# IMx6Q_EX.net
KiCad netlist of a schematic drawn in Altium Designer
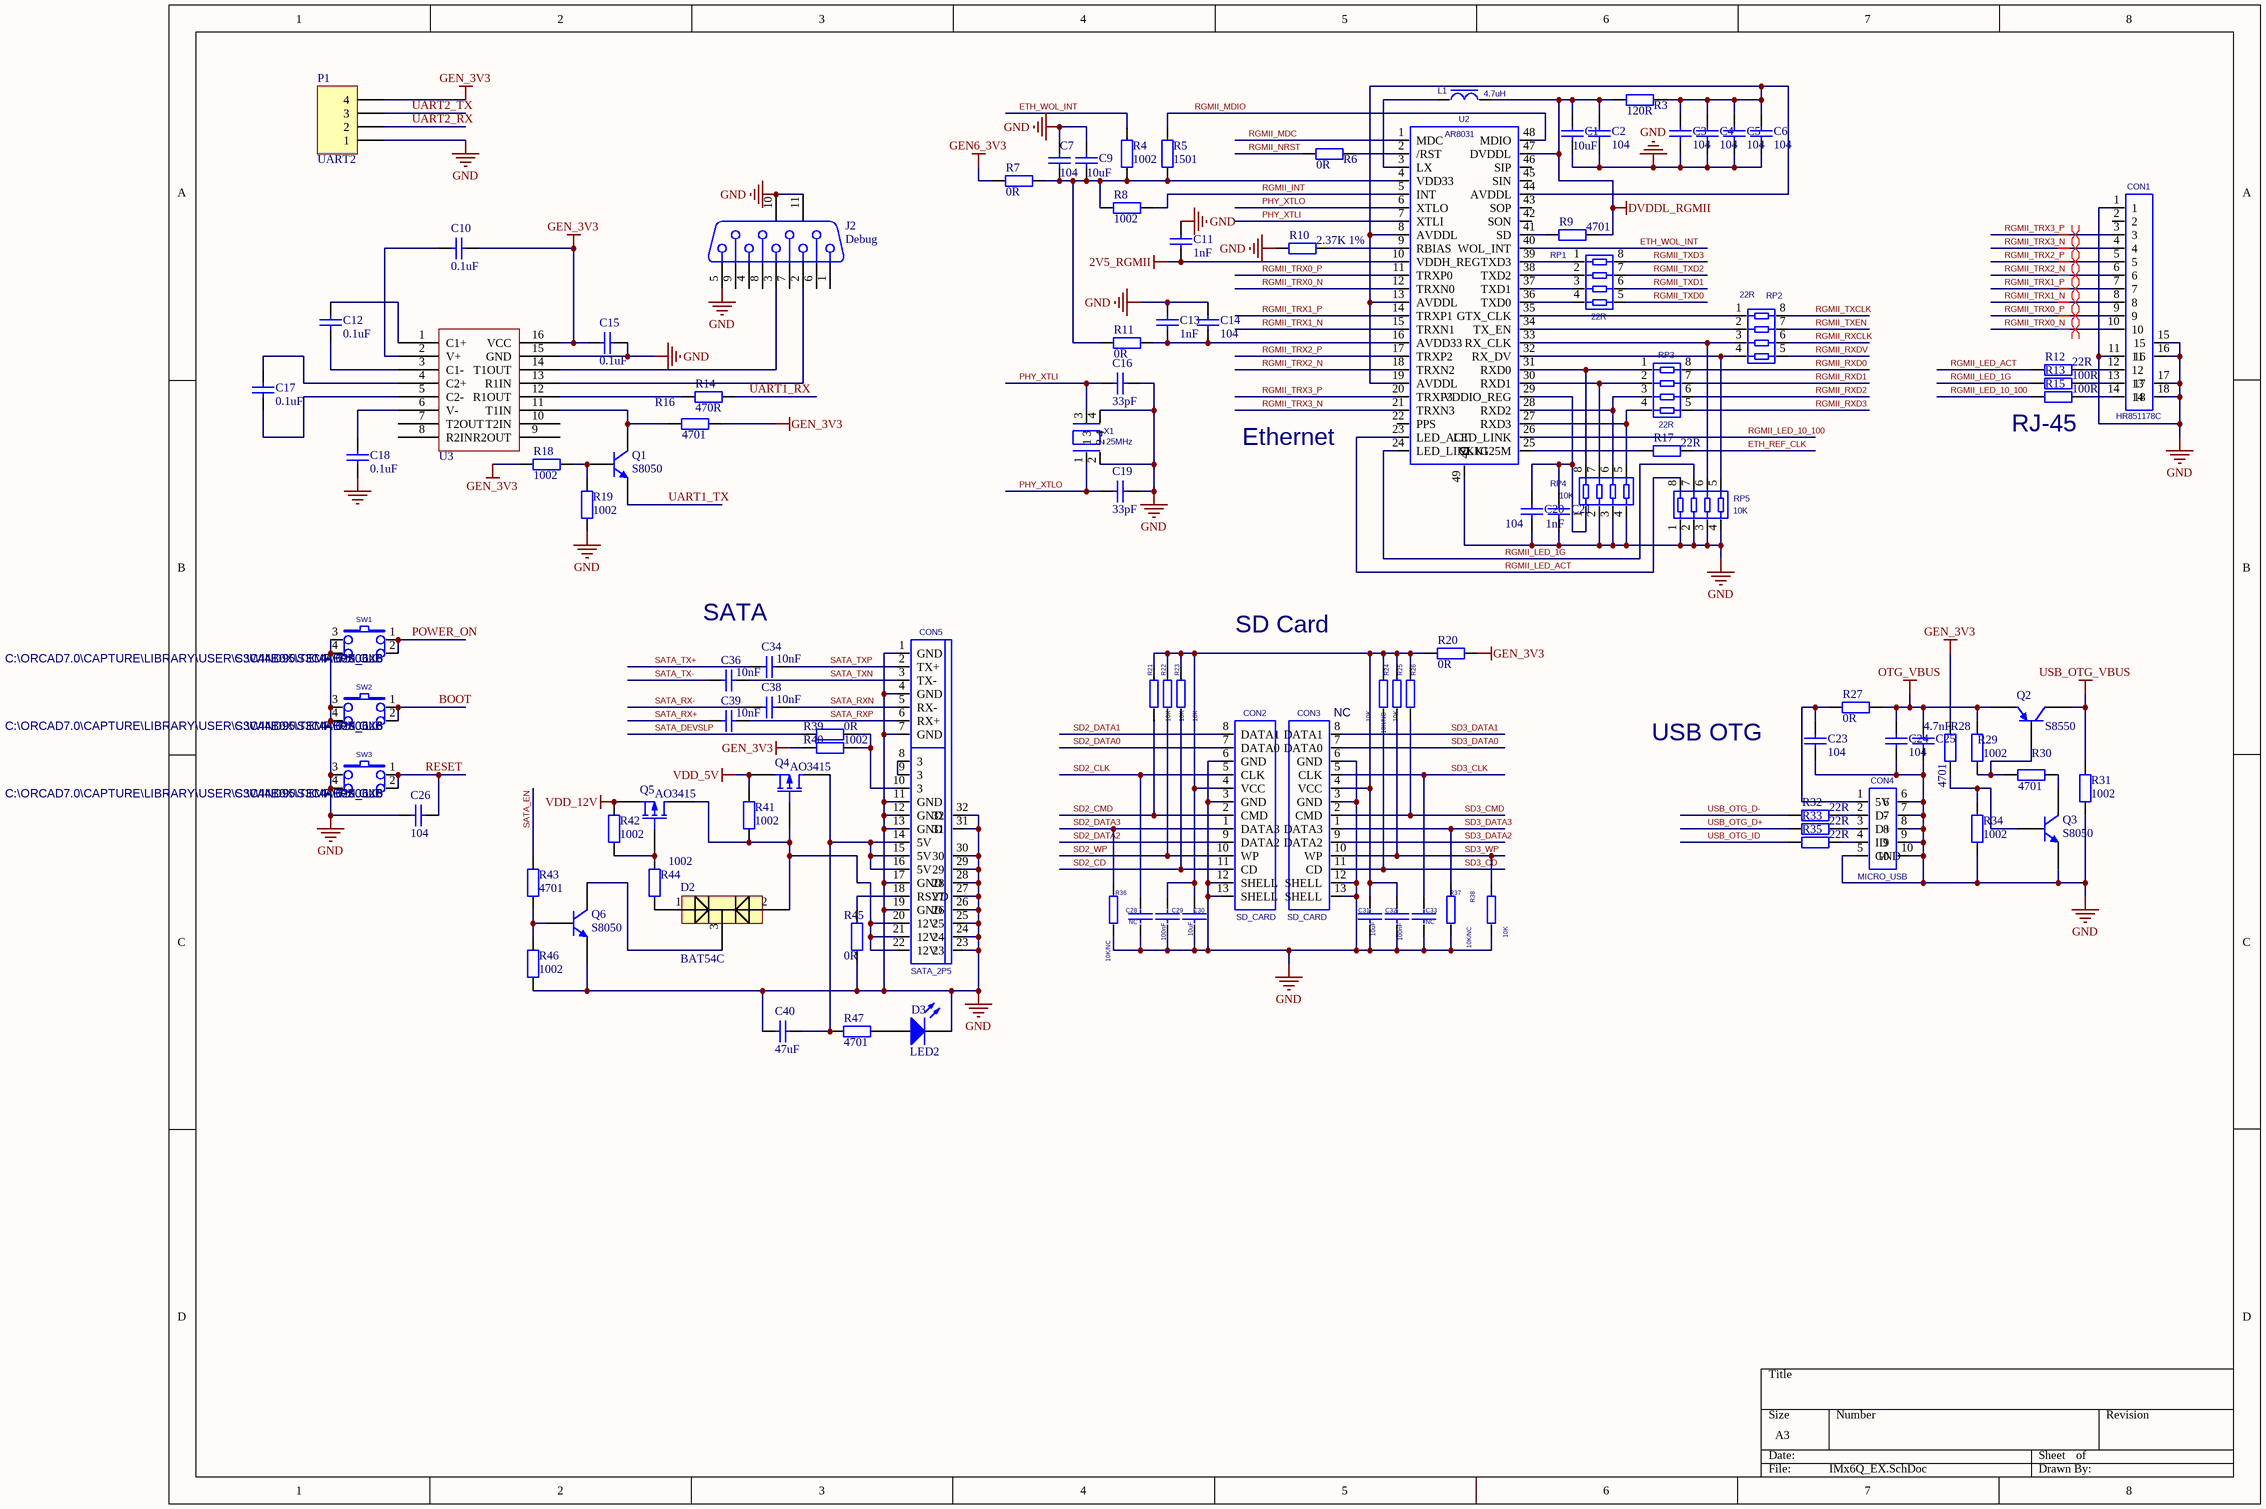
[diagram p0: IMx6Q_EX.SchDoc]

(export (version "E")
  (design (tool "Eeschema 10.0.6"))
  (components
    (comp (ref "C1")
      (value "10uF")
      (footprint "0805C")
      (description "Capacitor")
      (libsource (lib "Miscellaneous Devices") (part "Cap"))
    )
    (comp (ref "C2")
      (value "104")
      (footprint "0805C")
      (description "Capacitor")
      (libsource (lib "Miscellaneous Devices") (part "Cap"))
    )
    (comp (ref "C3")
      (value "104")
      (footprint "0805C")
      (description "Capacitor")
      (libsource (lib "Miscellaneous Devices") (part "Cap"))
    )
    (comp (ref "C4")
      (value "104")
      (footprint "0805C")
      (description "Capacitor")
      (libsource (lib "Miscellaneous Devices") (part "Cap"))
    )
    (comp (ref "C5")
      (value "104")
      (footprint "0805C")
      (description "Capacitor")
      (libsource (lib "Miscellaneous Devices") (part "Cap"))
    )
    (comp (ref "C6")
      (value "104")
      (footprint "0805C")
      (description "Capacitor")
      (libsource (lib "Miscellaneous Devices") (part "Cap"))
    )
    (comp (ref "C7")
      (value "104")
      (footprint "0805C")
      (description "Capacitor")
      (libsource (lib "Miscellaneous Devices") (part "Cap"))
    )
    (comp (ref "C9")
      (value "10uF")
      (footprint "0805C")
      (description "Capacitor")
      (libsource (lib "Miscellaneous Devices") (part "Cap"))
    )
    (comp (ref "C10") (value "0.1uF") (footprint "0805C") (libsource (lib "贴片电容电阻等") (part "电容")))
    (comp (ref "C11")
      (value "1nF")
      (footprint "0805C")
      (description "Capacitor")
      (libsource (lib "Miscellaneous Devices") (part "Cap"))
    )
    (comp (ref "C12") (value "0.1uF") (footprint "0805C") (libsource (lib "贴片电容电阻等") (part "电容")))
    (comp (ref "C13")
      (value "1nF")
      (footprint "0805C")
      (description "Capacitor")
      (libsource (lib "Miscellaneous Devices") (part "Cap"))
    )
    (comp (ref "C14")
      (value "104")
      (footprint "0805C")
      (description "Capacitor")
      (libsource (lib "Miscellaneous Devices") (part "Cap"))
    )
    (comp (ref "C15") (value "0.1uF") (footprint "0805C") (libsource (lib "贴片电容电阻等") (part "电容")))
    (comp (ref "C16")
      (value "33pF")
      (footprint "0805C")
      (description "Capacitor")
      (libsource (lib "Miscellaneous Devices") (part "Cap"))
    )
    (comp (ref "C17") (value "0.1uF") (footprint "0805C") (libsource (lib "贴片电容电阻等") (part "电容")))
    (comp (ref "C18") (value "0.1uF") (footprint "0805C") (libsource (lib "贴片电容电阻等") (part "电容")))
    (comp (ref "C19")
      (value "33pF")
      (footprint "0805C")
      (description "Capacitor")
      (libsource (lib "Miscellaneous Devices") (part "Cap"))
    )
    (comp (ref "C20")
      (value "104")
      (footprint "0805C")
      (description "Capacitor")
      (libsource (lib "Miscellaneous Devices") (part "Cap"))
    )
    (comp (ref "C21")
      (value "1nF")
      (footprint "0805C")
      (description "Capacitor")
      (libsource (lib "Miscellaneous Devices") (part "Cap"))
    )
    (comp (ref "C23")
      (value "104")
      (footprint "0805C")
      (description "Capacitor")
      (libsource (lib "Miscellaneous Devices") (part "Cap"))
    )
    (comp (ref "C24")
      (value "104")
      (footprint "0805C")
      (description "Capacitor")
      (libsource (lib "Miscellaneous Devices") (part "Cap"))
    )
    (comp (ref "C25")
      (value "4.7nF")
      (footprint "0805C")
      (description "Capacitor")
      (libsource (lib "Miscellaneous Devices") (part "Cap"))
    )
    (comp (ref "C26")
      (value "104")
      (footprint "0805C")
      (description "Capacitor")
      (libsource (lib "Miscellaneous Devices") (part "Cap"))
    )
    (comp (ref "C28")
      (value "NC")
      (footprint "0805C")
      (fields (field (name "Comment") "C_0603"))
      (libsource (lib "*") (part "C_0603"))
    )
    (comp (ref "C29")
      (value "100nF")
      (footprint "0805C")
      (fields (field (name "Comment") "C_0603"))
      (libsource (lib "*") (part "C_0603"))
    )
    (comp (ref "C30")
      (value "10uF")
      (footprint "0805C")
      (fields (field (name "Comment") "C_0603"))
      (libsource (lib "*") (part "C_0603"))
    )
    (comp (ref "C31")
      (value "10uF")
      (footprint "0805C")
      (fields (field (name "Comment") "C_0603"))
      (libsource (lib "*") (part "C_0603"))
    )
    (comp (ref "C32")
      (value "100nF")
      (footprint "0805C")
      (fields (field (name "Comment") "C_0603"))
      (libsource (lib "*") (part "C_0603"))
    )
    (comp (ref "C33")
      (value "NC")
      (footprint "0805C")
      (fields (field (name "Comment") "C_0603"))
      (libsource (lib "*") (part "C_0603"))
    )
    (comp (ref "C34")
      (value "10nF")
      (footprint "0805C")
      (description "Capacitor")
      (libsource (lib "Miscellaneous Devices") (part "Cap"))
    )
    (comp (ref "C36")
      (value "10nF")
      (footprint "0805C")
      (description "Capacitor")
      (libsource (lib "Miscellaneous Devices") (part "Cap"))
    )
    (comp (ref "C38")
      (value "10nF")
      (footprint "0805C")
      (description "Capacitor")
      (libsource (lib "Miscellaneous Devices") (part "Cap"))
    )
    (comp (ref "C39")
      (value "10nF")
      (footprint "0805C")
      (description "Capacitor")
      (libsource (lib "Miscellaneous Devices") (part "Cap"))
    )
    (comp (ref "C40")
      (value "47uF")
      (footprint "0805C")
      (description "Capacitor")
      (libsource (lib "Miscellaneous Devices") (part "Cap"))
    )
    (comp (ref "CON1") (value "HR851178C") (footprint "HR851178C") (libsource (lib "*") (part "HR851178C")))
    (comp (ref "CON2") (value "SD_CARD") (footprint "SD_CARD") (libsource (lib "*") (part "SD_CARD")))
    (comp (ref "CON3") (value "SD_CARD") (footprint "SD_CARD") (libsource (lib "*") (part "SD_CARD")))
    (comp (ref "CON4") (value "MICRO_USB") (footprint "MICRO_USB") (libsource (lib "*") (part "MICRO_USB")))
    (comp (ref "CON5")
      (value "SATA_2P5")
      (footprint "SATA_MICRO_2P5")
      (libsource (lib "*") (part "SATA_2P5"))
    )
    (comp (ref "D2") (value "BAT54C") (footprint "SOT-23-3") (libsource (lib "Schlib1") (part "BAT54C")))
    (comp (ref "D3")
      (value "LED2")
      (footprint "0805_LED")
      (description "Typical RED, GREEN, YELLOW, AMBER GaAs LED")
      (libsource (lib "Miscellaneous Devices") (part "LED2"))
    )
    (comp (ref "J2")
      (value "Debug")
      (footprint "DSUB1.385-2H9")
      (description "Receptacle Assembly, 9 Position, Right Angle")
      (libsource (lib "Miscellaneous Connectors") (part "D Connector 9"))
    )
    (comp (ref "L1")
      (value "4.7uH")
      (footprint "L_3-3")
      (fields (field (name "Comment") "L_3-3"))
      (libsource (lib "*") (part "L_3-3"))
    )
    (comp (ref "P1")
      (value "UART2")
      (footprint "HDR1X4")
      (description "Header, 4-Pin")
      (libsource (lib "Miscellaneous Connectors") (part "Header 4"))
    )
    (comp (ref "Q1")
      (value "S8050")
      (footprint "SOT23")
      (description "NPN General Purpose Amplifier")
      (libsource (lib "Miscellaneous Devices") (part "2N3904"))
    )
    (comp (ref "Q2")
      (value "S8550")
      (footprint "SOT23-S8550")
      (description "PNP Bipolar Transistor")
      (libsource (lib "Miscellaneous Devices") (part "PNP"))
    )
    (comp (ref "Q3")
      (value "S8050")
      (footprint "SOT23")
      (description "NPN General Purpose Amplifier")
      (libsource (lib "Miscellaneous Devices") (part "2N3904"))
    )
    (comp (ref "Q4")
      (value "AO3415")
      (footprint "SOT23-AO3415")
      (description "P-Channel MOSFET")
      (libsource (lib "Miscellaneous Devices") (part "MOSFET-P"))
    )
    (comp (ref "Q5")
      (value "AO3415")
      (footprint "SOT23-AO3415")
      (description "P-Channel MOSFET")
      (libsource (lib "Miscellaneous Devices") (part "MOSFET-P"))
    )
    (comp (ref "Q6")
      (value "S8050")
      (footprint "SOT23-AO3415")
      (description "NPN Bipolar Transistor")
      (libsource (lib "Miscellaneous Devices") (part "NPN"))
    )
    (comp (ref "R3") (value "120R") (footprint "0805R") (libsource (lib "") (part "电阻_1")))
    (comp (ref "R4") (value "1002") (footprint "0805R") (libsource (lib "贴片电容电阻等") (part "电阻")))
    (comp (ref "R5") (value "1501") (footprint "0805R") (libsource (lib "贴片电容电阻等") (part "电阻")))
    (comp (ref "R6") (value "0R") (footprint "0805R") (libsource (lib "") (part "电阻_1")))
    (comp (ref "R7") (value "0R") (footprint "0805R") (libsource (lib "") (part "电阻_1")))
    (comp (ref "R8") (value "1002") (footprint "0805R") (libsource (lib "") (part "电阻_2")))
    (comp (ref "R9")
      (value "4701")
      (footprint "0805R")
      (description "Resistor")
      (libsource (lib "Miscellaneous Devices") (part "Res2"))
    )
    (comp (ref "R10") (value "2.37K 1%") (footprint "0805R") (libsource (lib "") (part "电阻_1")))
    (comp (ref "R11") (value "0R") (footprint "0805R") (libsource (lib "") (part "电阻_1")))
    (comp (ref "R12")
      (value "22R")
      (footprint "0805R")
      (description "Resistor")
      (libsource (lib "Miscellaneous Devices") (part "Res2"))
    )
    (comp (ref "R13")
      (value "100R")
      (footprint "0805R")
      (description "Resistor")
      (libsource (lib "Miscellaneous Devices") (part "Res2"))
    )
    (comp (ref "R14") (value "470R") (footprint "0805R") (libsource (lib "") (part "电阻_1")))
    (comp (ref "R15")
      (value "100R")
      (footprint "0805R")
      (description "Resistor")
      (libsource (lib "Miscellaneous Devices") (part "Res2"))
    )
    (comp (ref "R16")
      (value "4701")
      (footprint "0805R")
      (description "Resistor")
      (libsource (lib "Miscellaneous Devices") (part "Res2"))
    )
    (comp (ref "R17")
      (value "22R")
      (footprint "0805R")
      (description "Resistor")
      (libsource (lib "Miscellaneous Devices") (part "Res2"))
    )
    (comp (ref "R18")
      (value "1002")
      (footprint "0805R")
      (description "Resistor")
      (libsource (lib "Miscellaneous Devices") (part "Res2"))
    )
    (comp (ref "R19")
      (value "1002")
      (footprint "0805R")
      (description "Resistor")
      (libsource (lib "") (part "Res2_2"))
    )
    (comp (ref "R20") (value "0R") (footprint "0805R") (libsource (lib "") (part "电阻_1")))
    (comp (ref "R21")
      (value "10K")
      (footprint "0805R")
      (fields (field (name "Comment") "R_0603"))
      (libsource (lib "*") (part "R_0603"))
    )
    (comp (ref "R22")
      (value "10K")
      (footprint "0805R")
      (fields (field (name "Comment") "R_0603"))
      (libsource (lib "*") (part "R_0603"))
    )
    (comp (ref "R23")
      (value "10K")
      (footprint "0805R")
      (fields (field (name "Comment") "R_0603"))
      (libsource (lib "*") (part "R_0603"))
    )
    (comp (ref "R24")
      (value "10K")
      (footprint "0805R")
      (fields (field (name "Comment") "R_0603"))
      (libsource (lib "*") (part "R_0603"))
    )
    (comp (ref "R25")
      (value "10K/NC")
      (footprint "0805R")
      (fields (field (name "Comment") "R_0603"))
      (libsource (lib "*") (part "R_0603"))
    )
    (comp (ref "R26")
      (value "10K")
      (footprint "0805R")
      (fields (field (name "Comment") "R_0603"))
      (libsource (lib "*") (part "R_0603"))
    )
    (comp (ref "R27") (value "0R") (footprint "0805R") (libsource (lib "") (part "电阻_1")))
    (comp (ref "R28") (value "4701") (footprint "0805R") (libsource (lib "贴片电容电阻等") (part "电阻")))
    (comp (ref "R29") (value "1002") (footprint "0805R") (libsource (lib "贴片电容电阻等") (part "电阻")))
    (comp (ref "R30") (value "4701") (footprint "0805R") (libsource (lib "") (part "电阻_2")))
    (comp (ref "R31") (value "1002") (footprint "0805R") (libsource (lib "贴片电容电阻等") (part "电阻")))
    (comp (ref "R32")
      (value "22R")
      (footprint "0805R")
      (description "Resistor")
      (libsource (lib "Miscellaneous Devices") (part "Res2"))
    )
    (comp (ref "R33")
      (value "22R")
      (footprint "0805R")
      (description "Resistor")
      (libsource (lib "Miscellaneous Devices") (part "Res2"))
    )
    (comp (ref "R34") (value "1002") (footprint "0805R") (libsource (lib "贴片电容电阻等") (part "电阻")))
    (comp (ref "R35")
      (value "22R")
      (footprint "0805R")
      (description "Resistor")
      (libsource (lib "Miscellaneous Devices") (part "Res2"))
    )
    (comp (ref "R36")
      (value "10K/NC")
      (footprint "0805R")
      (fields (field (name "Comment") "R_0603"))
      (libsource (lib "*") (part "R_0603"))
    )
    (comp (ref "R37")
      (value "10K/NC")
      (footprint "0805R")
      (fields (field (name "Comment") "R_0603"))
      (libsource (lib "*") (part "R_0603"))
    )
    (comp (ref "R38")
      (value "10K")
      (footprint "0805R")
      (fields (field (name "Comment") "R_0603"))
      (libsource (lib "*") (part "R_0603"))
    )
    (comp (ref "R39")
      (value "0R")
      (footprint "0805R")
      (description "Resistor")
      (libsource (lib "Miscellaneous Devices") (part "Res2"))
    )
    (comp (ref "R40")
      (value "1002")
      (footprint "0805R")
      (description "Resistor")
      (libsource (lib "Miscellaneous Devices") (part "Res2"))
    )
    (comp (ref "R41")
      (value "1002")
      (footprint "0805R")
      (description "Resistor")
      (libsource (lib "") (part "Res2_2"))
    )
    (comp (ref "R42")
      (value "1002")
      (footprint "0805R")
      (description "Resistor")
      (libsource (lib "") (part "Res2_2"))
    )
    (comp (ref "R43")
      (value "4701")
      (footprint "0805R")
      (description "Resistor")
      (libsource (lib "") (part "Res2_2"))
    )
    (comp (ref "R44")
      (value "1002")
      (footprint "0805R")
      (description "Resistor")
      (libsource (lib "") (part "Res2_3"))
    )
    (comp (ref "R45")
      (value "0R")
      (footprint "0805R")
      (description "Resistor")
      (libsource (lib "") (part "Res2_2"))
    )
    (comp (ref "R46")
      (value "1002")
      (footprint "0805R")
      (description "Resistor")
      (libsource (lib "") (part "Res2_2"))
    )
    (comp (ref "R47")
      (value "4701")
      (footprint "0805R")
      (description "Resistor")
      (libsource (lib "") (part "Res2_1"))
    )
    (comp (ref "RP1")
      (value "22R")
      (footprint "RP4_0603")
      (fields (field (name "Comment") "RP4_0603"))
      (libsource (lib "*") (part "RP4_0603"))
    )
    (comp (ref "RP2")
      (value "22R")
      (footprint "RP4_0603")
      (fields (field (name "Comment") "RP4_0603"))
      (libsource (lib "*") (part "RP4_0603"))
    )
    (comp (ref "RP3")
      (value "22R")
      (footprint "RP4_0603")
      (fields (field (name "Comment") "RP4_0603"))
      (libsource (lib "*") (part "RP4_0603"))
    )
    (comp (ref "RP4")
      (value "10K")
      (footprint "RP4_0603")
      (fields (field (name "Comment") "RP4_0603"))
      (libsource (lib "*") (part "RP4_0603"))
    )
    (comp (ref "RP5")
      (value "10K")
      (footprint "RP4_0603")
      (fields (field (name "Comment") "RP4_0603"))
      (libsource (lib "*") (part "RP4_0603"))
    )
    (comp (ref "SW1")
      (value "ALPS_6X6")
      (footprint "ALPS_6*6")
      (fields
        (field (name "SOURCE PATH") "C~{:}ORCAD7.~{0}CAPTUR~{E}LIBRAR~{Y}USE~{R}S3C44B0~{X}S3C44B0X.OLB")
        (field (name "SDTSOURCELIBNAME") "C~{:}WIND9~{5}TEM~{P}6200.LIB")
      )
      (libsource (lib "*") (part "ALPS_6X6"))
    )
    (comp (ref "SW2")
      (value "ALPS_6X6")
      (footprint "ALPS_6*6")
      (fields
        (field (name "SOURCE PATH") "C~{:}ORCAD7.~{0}CAPTUR~{E}LIBRAR~{Y}USE~{R}S3C44B0~{X}S3C44B0X.OLB")
        (field (name "SDTSOURCELIBNAME") "C~{:}WIND9~{5}TEM~{P}6200.LIB")
      )
      (libsource (lib "*") (part "ALPS_6X6"))
    )
    (comp (ref "SW3")
      (value "ALPS_6X6")
      (footprint "ALPS_6*6")
      (fields
        (field (name "SOURCE PATH") "C~{:}ORCAD7.~{0}CAPTUR~{E}LIBRAR~{Y}USE~{R}S3C44B0~{X}S3C44B0X.OLB")
        (field (name "SDTSOURCELIBNAME") "C~{:}WIND9~{5}TEM~{P}6200.LIB")
      )
      (libsource (lib "*") (part "ALPS_6X6"))
    )
    (comp (ref "U2") (value "AR8031") (footprint "QFN-48") (libsource (lib "*") (part "AR8031")))
    (comp (ref "U3") (value "MAX232") (footprint "SOP16") (libsource (lib "芯片") (part "MAX232")))
    (comp (ref "X1")
      (value "25MHz")
      (footprint "OSC_3225_4P")
      (fields (field (name "Comment") "OSC_3225_4P"))
      (libsource (lib "*") (part "OSC_3225_4P"))
    )
  )
  (nets
    (net (code "1") (name "/BOOT") (class "Default")
      (node (ref "SW2") (pin "1") (pinfunction "1_1") (pintype "passive"))
      (node (ref "SW2") (pin "2") (pinfunction "2_2") (pintype "passive"))
    )
    (net (code "2") (name "/ETH_REF_CLK") (class "Default")
      (node (ref "R17") (pin "1") (pinfunction "1_1") (pintype "passive"))
    )
    (net (code "3") (name "/ETH_WOL_INT") (class "Default")
      (node (ref "R4") (pin "2") (pinfunction "2_2") (pintype "passive"))
      (node (ref "U2") (pin "40") (pinfunction "WOL_INT_40") (pintype "passive"))
    )
    (net (code "4") (name "/PHY_XTLI") (class "Default")
      (node (ref "C16") (pin "1") (pinfunction "1_1") (pintype "passive"))
      (node (ref "U2") (pin "7") (pinfunction "XTLI_7") (pintype "passive"))
      (node (ref "X1") (pin "3") (pinfunction "3_3") (pintype "passive"))
    )
    (net (code "5") (name "/PHY_XTLO") (class "Default")
      (node (ref "C19") (pin "1") (pinfunction "1_1") (pintype "passive"))
      (node (ref "U2") (pin "6") (pinfunction "XTLO_6") (pintype "passive"))
      (node (ref "X1") (pin "1") (pinfunction "1_1") (pintype "passive"))
    )
    (net (code "6") (name "/POWER_ON") (class "Default")
      (node (ref "SW1") (pin "1") (pinfunction "1_1") (pintype "passive"))
      (node (ref "SW1") (pin "2") (pinfunction "2_2") (pintype "passive"))
    )
    (net (code "7") (name "/RESET") (class "Default")
      (node (ref "C26") (pin "2") (pinfunction "2_2") (pintype "passive"))
      (node (ref "SW3") (pin "1") (pinfunction "1_1") (pintype "passive"))
      (node (ref "SW3") (pin "2") (pinfunction "2_2") (pintype "passive"))
    )
    (net (code "8") (name "/RGMII_INT") (class "Default")
      (node (ref "R8") (pin "1") (pinfunction "1_1") (pintype "passive"))
      (node (ref "U2") (pin "5") (pinfunction "INT_5") (pintype "passive"))
    )
    (net (code "9") (name "/RGMII_LED_1G") (class "Default")
      (node (ref "R13") (pin "2") (pinfunction "2_2") (pintype "passive"))
      (node (ref "RP5") (pin "7") (pinfunction "7_7") (pintype "passive"))
      (node (ref "U2") (pin "24") (pinfunction "LED_LINK1G_24") (pintype "passive"))
    )
    (net (code "10") (name "/RGMII_LED_10_100") (class "Default")
      (node (ref "R15") (pin "2") (pinfunction "2_2") (pintype "passive"))
      (node (ref "U2") (pin "26") (pinfunction "LED_LINK_26") (pintype "passive"))
    )
    (net (code "11") (name "/RGMII_LED_ACT") (class "Default")
      (node (ref "R12") (pin "2") (pinfunction "2_2") (pintype "passive"))
      (node (ref "RP5") (pin "8") (pinfunction "8_8") (pintype "passive"))
      (node (ref "U2") (pin "23") (pinfunction "LED_ACT_23") (pintype "passive"))
    )
    (net (code "12") (name "/RGMII_MDC") (class "Default")
      (node (ref "U2") (pin "1") (pinfunction "MDC_1") (pintype "passive"))
    )
    (net (code "13") (name "/RGMII_MDIO") (class "Default")
      (node (ref "R5") (pin "2") (pinfunction "2_2") (pintype "passive"))
      (node (ref "U2") (pin "48") (pinfunction "MDIO_48") (pintype "passive"))
    )
    (net (code "14") (name "/RGMII_NRST") (class "Default")
      (node (ref "R6") (pin "1") (pinfunction "1_1") (pintype "passive"))
    )
    (net (code "15") (name "/RGMII_RXCLK") (class "Default")
      (node (ref "RP2") (pin "6") (pinfunction "6_6") (pintype "passive"))
    )
    (net (code "16") (name "/RGMII_RXD0") (class "Default")
      (node (ref "RP3") (pin "8") (pinfunction "8_8") (pintype "passive"))
    )
    (net (code "17") (name "/RGMII_RXD1") (class "Default")
      (node (ref "RP3") (pin "7") (pinfunction "7_7") (pintype "passive"))
    )
    (net (code "18") (name "/RGMII_RXD2") (class "Default")
      (node (ref "RP3") (pin "6") (pinfunction "6_6") (pintype "passive"))
    )
    (net (code "19") (name "/RGMII_RXD3") (class "Default")
      (node (ref "RP3") (pin "5") (pinfunction "5_5") (pintype "passive"))
    )
    (net (code "20") (name "/RGMII_RXDV") (class "Default")
      (node (ref "RP2") (pin "5") (pinfunction "5_5") (pintype "passive"))
    )
    (net (code "21") (name "/RGMII_TRX0_N") (class "Default")
      (node (ref "CON1") (pin "10") (pinfunction "10_10") (pintype "passive"))
      (node (ref "U2") (pin "12") (pinfunction "TRXN0_12") (pintype "passive"))
    )
    (net (code "22") (name "/RGMII_TRX0_P") (class "Default")
      (node (ref "CON1") (pin "9") (pinfunction "9_9") (pintype "passive"))
      (node (ref "U2") (pin "11") (pinfunction "TRXP0_11") (pintype "passive"))
    )
    (net (code "23") (name "/RGMII_TRX1_N") (class "Default")
      (node (ref "CON1") (pin "8") (pinfunction "8_8") (pintype "passive"))
      (node (ref "U2") (pin "15") (pinfunction "TRXN1_15") (pintype "passive"))
    )
    (net (code "24") (name "/RGMII_TRX1_P") (class "Default")
      (node (ref "CON1") (pin "7") (pinfunction "7_7") (pintype "passive"))
      (node (ref "U2") (pin "14") (pinfunction "TRXP1_14") (pintype "passive"))
    )
    (net (code "25") (name "/RGMII_TRX2_N") (class "Default")
      (node (ref "CON1") (pin "6") (pinfunction "6_6") (pintype "passive"))
      (node (ref "U2") (pin "18") (pinfunction "TRXN2_18") (pintype "passive"))
    )
    (net (code "26") (name "/RGMII_TRX2_P") (class "Default")
      (node (ref "CON1") (pin "5") (pinfunction "5_5") (pintype "passive"))
      (node (ref "U2") (pin "17") (pinfunction "TRXP2_17") (pintype "passive"))
    )
    (net (code "27") (name "/RGMII_TRX3_N") (class "Default")
      (node (ref "CON1") (pin "4") (pinfunction "4_4") (pintype "passive"))
      (node (ref "U2") (pin "21") (pinfunction "TRXN3_21") (pintype "passive"))
    )
    (net (code "28") (name "/RGMII_TRX3_P") (class "Default")
      (node (ref "CON1") (pin "3") (pinfunction "3_3") (pintype "passive"))
      (node (ref "U2") (pin "20") (pinfunction "TRXP3_20") (pintype "passive"))
    )
    (net (code "29") (name "/RGMII_TXCLK") (class "Default")
      (node (ref "RP2") (pin "8") (pinfunction "8_8") (pintype "passive"))
    )
    (net (code "30") (name "/RGMII_TXD0") (class "Default")
      (node (ref "RP1") (pin "5") (pinfunction "5_5") (pintype "passive"))
    )
    (net (code "31") (name "/RGMII_TXD1") (class "Default")
      (node (ref "RP1") (pin "6") (pinfunction "6_6") (pintype "passive"))
    )
    (net (code "32") (name "/RGMII_TXD2") (class "Default")
      (node (ref "RP1") (pin "7") (pinfunction "7_7") (pintype "passive"))
    )
    (net (code "33") (name "/RGMII_TXD3") (class "Default")
      (node (ref "RP1") (pin "8") (pinfunction "8_8") (pintype "passive"))
    )
    (net (code "34") (name "/RGMII_TXEN") (class "Default")
      (node (ref "RP2") (pin "7") (pinfunction "7_7") (pintype "passive"))
    )
    (net (code "35") (name "/SATA_DEVSLP") (class "Default")
      (node (ref "R39") (pin "2") (pinfunction "2_2") (pintype "passive"))
    )
    (net (code "36") (name "/SATA_EN") (class "Default")
      (node (ref "R43") (pin "1") (pinfunction "1_1") (pintype "passive"))
    )
    (net (code "37") (name "/SATA_RX+") (class "Default")
      (node (ref "C39") (pin "1") (pinfunction "1_1") (pintype "passive"))
    )
    (net (code "38") (name "/SATA_RX-") (class "Default")
      (node (ref "C38") (pin "1") (pinfunction "1_1") (pintype "passive"))
    )
    (net (code "39") (name "/SATA_RXN") (class "Default")
      (node (ref "C38") (pin "2") (pinfunction "2_2") (pintype "passive"))
      (node (ref "CON5") (pin "5") (pinfunction "RX-_5") (pintype "passive"))
    )
    (net (code "40") (name "/SATA_RXP") (class "Default")
      (node (ref "C39") (pin "2") (pinfunction "2_2") (pintype "passive"))
      (node (ref "CON5") (pin "6") (pinfunction "RX+_6") (pintype "passive"))
    )
    (net (code "41") (name "/SATA_TX+") (class "Default")
      (node (ref "C34") (pin "1") (pinfunction "1_1") (pintype "passive"))
    )
    (net (code "42") (name "/SATA_TX-") (class "Default")
      (node (ref "C36") (pin "1") (pinfunction "1_1") (pintype "passive"))
    )
    (net (code "43") (name "/SATA_TXN") (class "Default")
      (node (ref "C36") (pin "2") (pinfunction "2_2") (pintype "passive"))
      (node (ref "CON5") (pin "3") (pinfunction "TX-_3") (pintype "passive"))
    )
    (net (code "44") (name "/SATA_TXP") (class "Default")
      (node (ref "C34") (pin "2") (pinfunction "2_2") (pintype "passive"))
      (node (ref "CON5") (pin "2") (pinfunction "TX+_2") (pintype "passive"))
    )
    (net (code "45") (name "/SD2_CD") (class "Default")
      (node (ref "CON2") (pin "11") (pinfunction "CD_11") (pintype "passive"))
      (node (ref "R23") (pin "1") (pinfunction "1_1") (pintype "passive"))
    )
    (net (code "46") (name "/SD2_CLK") (class "Default")
      (node (ref "C28") (pin "2") (pinfunction "2_2") (pintype "passive"))
      (node (ref "CON2") (pin "5") (pinfunction "CLK_5") (pintype "passive"))
    )
    (net (code "47") (name "/SD2_CMD") (class "Default")
      (node (ref "CON2") (pin "2") (pinfunction "CMD_2") (pintype "passive"))
      (node (ref "R21") (pin "1") (pinfunction "1_1") (pintype "passive"))
    )
    (net (code "48") (name "/SD2_DATA0") (class "Default")
      (node (ref "CON2") (pin "7") (pinfunction "DATA0_7") (pintype "passive"))
    )
    (net (code "49") (name "/SD2_DATA1") (class "Default")
      (node (ref "CON2") (pin "8") (pinfunction "DATA1_8") (pintype "passive"))
    )
    (net (code "50") (name "/SD2_DATA2") (class "Default")
      (node (ref "CON2") (pin "9") (pinfunction "DATA2_9") (pintype "passive"))
    )
    (net (code "51") (name "/SD2_DATA3") (class "Default")
      (node (ref "CON2") (pin "1") (pinfunction "DATA3_1") (pintype "passive"))
      (node (ref "R36") (pin "2") (pinfunction "2_2") (pintype "passive"))
    )
    (net (code "52") (name "/SD2_WP") (class "Default")
      (node (ref "CON2") (pin "10") (pinfunction "WP_10") (pintype "passive"))
      (node (ref "R22") (pin "1") (pinfunction "1_1") (pintype "passive"))
    )
    (net (code "53") (name "/SD3_CD") (class "Default")
      (node (ref "CON3") (pin "11") (pinfunction "CD_11") (pintype "passive"))
      (node (ref "R24") (pin "1") (pinfunction "1_1") (pintype "passive"))
    )
    (net (code "54") (name "/SD3_CLK") (class "Default")
      (node (ref "C33") (pin "2") (pinfunction "2_2") (pintype "passive"))
      (node (ref "CON3") (pin "5") (pinfunction "CLK_5") (pintype "passive"))
    )
    (net (code "55") (name "/SD3_CMD") (class "Default")
      (node (ref "CON3") (pin "2") (pinfunction "CMD_2") (pintype "passive"))
      (node (ref "R26") (pin "1") (pinfunction "1_1") (pintype "passive"))
    )
    (net (code "56") (name "/SD3_DATA0") (class "Default")
      (node (ref "CON3") (pin "7") (pinfunction "DATA0_7") (pintype "passive"))
    )
    (net (code "57") (name "/SD3_DATA1") (class "Default")
      (node (ref "CON3") (pin "8") (pinfunction "DATA1_8") (pintype "passive"))
    )
    (net (code "58") (name "/SD3_DATA2") (class "Default")
      (node (ref "CON3") (pin "9") (pinfunction "DATA2_9") (pintype "passive"))
    )
    (net (code "59") (name "/SD3_DATA3") (class "Default")
      (node (ref "CON3") (pin "1") (pinfunction "DATA3_1") (pintype "passive"))
      (node (ref "R37") (pin "2") (pinfunction "2_2") (pintype "passive"))
    )
    (net (code "60") (name "/SD3_WP") (class "Default")
      (node (ref "CON3") (pin "10") (pinfunction "WP_10") (pintype "passive"))
      (node (ref "R25") (pin "1") (pinfunction "1_1") (pintype "passive"))
      (node (ref "R38") (pin "2") (pinfunction "2_2") (pintype "passive"))
    )
    (net (code "61") (name "/UART1_RX") (class "Default")
      (node (ref "R14") (pin "2") (pinfunction "2_2") (pintype "passive"))
    )
    (net (code "62") (name "/UART1_TX") (class "Default")
      (node (ref "Q1") (pin "1") (pinfunction "E_1") (pintype "passive"))
    )
    (net (code "63") (name "/UART2_RX") (class "Default")
      (node (ref "P1") (pin "2") (pinfunction "2_2") (pintype "passive"))
    )
    (net (code "64") (name "/UART2_TX") (class "Default")
      (node (ref "P1") (pin "3") (pinfunction "3_3") (pintype "passive"))
    )
    (net (code "65") (name "/USB_OTG_D+") (class "Default")
      (node (ref "R33") (pin "2") (pinfunction "2_2") (pintype "passive"))
    )
    (net (code "66") (name "/USB_OTG_D-") (class "Default")
      (node (ref "R32") (pin "2") (pinfunction "2_2") (pintype "passive"))
    )
    (net (code "67") (name "/USB_OTG_ID") (class "Default")
      (node (ref "R35") (pin "2") (pinfunction "2_2") (pintype "passive"))
    )
    (net (code "68") (name "2V5_RGMII") (class "Default")
      (node (ref "C11") (pin "2") (pinfunction "2_2") (pintype "passive"))
      (node (ref "U2") (pin "10") (pinfunction "VDDH_REG_10") (pintype "passive"))
    )
    (net (code "69") (name "DVDDL_RGMII") (class "Default")
      (node (ref "C1") (pin "1") (pinfunction "1_1") (pintype "passive"))
      (node (ref "C2") (pin "1") (pinfunction "1_1") (pintype "passive"))
      (node (ref "L1") (pin "2") (pinfunction "2_2") (pintype "passive"))
      (node (ref "R3") (pin "1") (pinfunction "1_1") (pintype "passive"))
      (node (ref "R9") (pin "1") (pinfunction "1_1") (pintype "passive"))
      (node (ref "U2") (pin "47") (pinfunction "DVDDL_47") (pintype "passive"))
    )
    (net (code "70") (name "GEN6_3V3") (class "Default")
      (node (ref "R7") (pin "1") (pinfunction "1_1") (pintype "passive"))
    )
    (net (code "71") (name "GEN_3V3") (class "Default")
      (node (ref "C10") (pin "1") (pinfunction "1_1") (pintype "passive"))
      (node (ref "C15") (pin "2") (pinfunction "2_2") (pintype "passive"))
      (node (ref "P1") (pin "4") (pinfunction "4_4") (pintype "passive"))
      (node (ref "R16") (pin "1") (pinfunction "1_1") (pintype "passive"))
      (node (ref "R18") (pin "2") (pinfunction "2_2") (pintype "passive"))
      (node (ref "R20") (pin "2") (pinfunction "2_2") (pintype "passive"))
      (node (ref "R28") (pin "2") (pinfunction "2_2") (pintype "passive"))
      (node (ref "R40") (pin "2") (pinfunction "2_2") (pintype "passive"))
      (node (ref "U3") (pin "16") (pinfunction "VCC_16") (pintype "passive"))
    )
    (net (code "72") (name "GND") (class "Default")
      (node (ref "C1") (pin "2") (pinfunction "2_2") (pintype "passive"))
      (node (ref "C11") (pin "1") (pinfunction "1_1") (pintype "passive"))
      (node (ref "C13") (pin "1") (pinfunction "1_1") (pintype "passive"))
      (node (ref "C14") (pin "1") (pinfunction "1_1") (pintype "passive"))
      (node (ref "C15") (pin "1") (pinfunction "1_1") (pintype "passive"))
      (node (ref "C16") (pin "2") (pinfunction "2_2") (pintype "passive"))
      (node (ref "C18") (pin "1") (pinfunction "1_1") (pintype "passive"))
      (node (ref "C19") (pin "2") (pinfunction "2_2") (pintype "passive"))
      (node (ref "C2") (pin "2") (pinfunction "2_2") (pintype "passive"))
      (node (ref "C20") (pin "2") (pinfunction "2_2") (pintype "passive"))
      (node (ref "C21") (pin "2") (pinfunction "2_2") (pintype "passive"))
      (node (ref "C23") (pin "2") (pinfunction "2_2") (pintype "passive"))
      (node (ref "C24") (pin "2") (pinfunction "2_2") (pintype "passive"))
      (node (ref "C25") (pin "2") (pinfunction "2_2") (pintype "passive"))
      (node (ref "C26") (pin "1") (pinfunction "1_1") (pintype "passive"))
      (node (ref "C28") (pin "1") (pinfunction "1_1") (pintype "passive"))
      (node (ref "C29") (pin "1") (pinfunction "1_1") (pintype "passive"))
      (node (ref "C3") (pin "2") (pinfunction "2_2") (pintype "passive"))
      (node (ref "C30") (pin "1") (pinfunction "1_1") (pintype "passive"))
      (node (ref "C31") (pin "1") (pinfunction "1_1") (pintype "passive"))
      (node (ref "C32") (pin "1") (pinfunction "1_1") (pintype "passive"))
      (node (ref "C33") (pin "1") (pinfunction "1_1") (pintype "passive"))
      (node (ref "C4") (pin "2") (pinfunction "2_2") (pintype "passive"))
      (node (ref "C40") (pin "2") (pinfunction "2_2") (pintype "passive"))
      (node (ref "C5") (pin "2") (pinfunction "2_2") (pintype "passive"))
      (node (ref "C6") (pin "2") (pinfunction "2_2") (pintype "passive"))
      (node (ref "C7") (pin "2") (pinfunction "2_2") (pintype "passive"))
      (node (ref "C9") (pin "2") (pinfunction "2_2") (pintype "passive"))
      (node (ref "CON1") (pin "1") (pinfunction "1_1") (pintype "passive"))
      (node (ref "CON1") (pin "11") (pinfunction "11_11") (pintype "passive"))
      (node (ref "CON1") (pin "15") (pinfunction "15_15") (pintype "passive"))
      (node (ref "CON1") (pin "16") (pinfunction "16_16") (pintype "passive"))
      (node (ref "CON1") (pin "17") (pinfunction "17_17") (pintype "passive"))
      (node (ref "CON1") (pin "18") (pinfunction "18_18") (pintype "passive"))
      (node (ref "CON2") (pin "12") (pinfunction "SHELL_12") (pintype "passive"))
      (node (ref "CON2") (pin "13") (pinfunction "SHELL_13") (pintype "passive"))
      (node (ref "CON2") (pin "3") (pinfunction "GND_3") (pintype "passive"))
      (node (ref "CON2") (pin "6") (pinfunction "GND_6") (pintype "passive"))
      (node (ref "CON3") (pin "12") (pinfunction "SHELL_12") (pintype "passive"))
      (node (ref "CON3") (pin "13") (pinfunction "SHELL_13") (pintype "passive"))
      (node (ref "CON3") (pin "3") (pinfunction "GND_3") (pintype "passive"))
      (node (ref "CON3") (pin "6") (pinfunction "GND_6") (pintype "passive"))
      (node (ref "CON4") (pin "10") (pinfunction "10_10") (pintype "passive"))
      (node (ref "CON4") (pin "5") (pinfunction "GND_5") (pintype "passive"))
      (node (ref "CON4") (pin "6") (pinfunction "6_6") (pintype "passive"))
      (node (ref "CON4") (pin "7") (pinfunction "7_7") (pintype "passive"))
      (node (ref "CON4") (pin "8") (pinfunction "8_8") (pintype "passive"))
      (node (ref "CON4") (pin "9") (pinfunction "9_9") (pintype "passive"))
      (node (ref "CON5") (pin "1") (pinfunction "GND_1") (pintype "passive"))
      (node (ref "CON5") (pin "11") (pinfunction "GND_11") (pintype "passive"))
      (node (ref "CON5") (pin "12") (pinfunction "GND_12") (pintype "passive"))
      (node (ref "CON5") (pin "13") (pinfunction "GND_13") (pintype "passive"))
      (node (ref "CON5") (pin "17") (pinfunction "GND_17") (pintype "passive"))
      (node (ref "CON5") (pin "19") (pinfunction "GND_19") (pintype "passive"))
      (node (ref "CON5") (pin "23") (pinfunction "23_23") (pintype "passive"))
      (node (ref "CON5") (pin "24") (pinfunction "24_24") (pintype "passive"))
      (node (ref "CON5") (pin "25") (pinfunction "25_25") (pintype "passive"))
      (node (ref "CON5") (pin "26") (pinfunction "26_26") (pintype "passive"))
      (node (ref "CON5") (pin "27") (pinfunction "27_27") (pintype "passive"))
      (node (ref "CON5") (pin "28") (pinfunction "28_28") (pintype "passive"))
      (node (ref "CON5") (pin "29") (pinfunction "29_29") (pintype "passive"))
      (node (ref "CON5") (pin "30") (pinfunction "30_30") (pintype "passive"))
      (node (ref "CON5") (pin "31") (pinfunction "31_31") (pintype "passive"))
      (node (ref "CON5") (pin "32") (pinfunction "32_32") (pintype "passive"))
      (node (ref "CON5") (pin "4") (pinfunction "GND_4") (pintype "passive"))
      (node (ref "CON5") (pin "7") (pinfunction "GND_7") (pintype "passive"))
      (node (ref "D3") (pin "2") (pinfunction "K_2") (pintype "passive"))
      (node (ref "J2") (pin "10") (pinfunction "MH1_10") (pintype "passive"))
      (node (ref "J2") (pin "11") (pinfunction "MH2_11") (pintype "passive"))
      (node (ref "J2") (pin "5") (pinfunction "5_5") (pintype "passive"))
      (node (ref "P1") (pin "1") (pinfunction "1_1") (pintype "passive"))
      (node (ref "Q3") (pin "1") (pinfunction "E_1") (pintype "passive"))
      (node (ref "Q6") (pin "3") (pinfunction "E_3") (pintype "passive"))
      (node (ref "R10") (pin "1") (pinfunction "1_1") (pintype "passive"))
      (node (ref "R19") (pin "2") (pinfunction "2_2") (pintype "passive"))
      (node (ref "R31") (pin "1") (pinfunction "1_1") (pintype "passive"))
      (node (ref "R34") (pin "1") (pinfunction "1_1") (pintype "passive"))
      (node (ref "R36") (pin "1") (pinfunction "1_1") (pintype "passive"))
      (node (ref "R37") (pin "1") (pinfunction "1_1") (pintype "passive"))
      (node (ref "R38") (pin "1") (pinfunction "1_1") (pintype "passive"))
      (node (ref "R45") (pin "2") (pinfunction "2_2") (pintype "passive"))
      (node (ref "R46") (pin "2") (pinfunction "2_2") (pintype "passive"))
      (node (ref "RP4") (pin "2") (pinfunction "2_2") (pintype "passive"))
      (node (ref "RP4") (pin "3") (pinfunction "3_3") (pintype "passive"))
      (node (ref "RP4") (pin "4") (pinfunction "4_4") (pintype "passive"))
      (node (ref "RP5") (pin "1") (pinfunction "1_1") (pintype "passive"))
      (node (ref "RP5") (pin "2") (pinfunction "2_2") (pintype "passive"))
      (node (ref "RP5") (pin "3") (pinfunction "3_3") (pintype "passive"))
      (node (ref "RP5") (pin "4") (pinfunction "4_4") (pintype "passive"))
      (node (ref "SW1") (pin "3") (pinfunction "3_3") (pintype "passive"))
      (node (ref "SW1") (pin "4") (pinfunction "4_4") (pintype "passive"))
      (node (ref "SW2") (pin "3") (pinfunction "3_3") (pintype "passive"))
      (node (ref "SW2") (pin "4") (pinfunction "4_4") (pintype "passive"))
      (node (ref "SW3") (pin "3") (pinfunction "3_3") (pintype "passive"))
      (node (ref "SW3") (pin "4") (pinfunction "4_4") (pintype "passive"))
      (node (ref "U2") (pin "49") (pinfunction "49_49") (pintype "passive"))
      (node (ref "U3") (pin "15") (pinfunction "GND_15") (pintype "passive"))
      (node (ref "X1") (pin "2") (pinfunction "2_2") (pintype "passive"))
      (node (ref "X1") (pin "4") (pinfunction "4_4") (pintype "passive"))
    )
    (net (code "73") (name "Net-(C3-Pad1)") (class "Default")
      (node (ref "C3") (pin "1") (pinfunction "1_1") (pintype "passive"))
      (node (ref "C4") (pin "1") (pinfunction "1_1") (pintype "passive"))
      (node (ref "C5") (pin "1") (pinfunction "1_1") (pintype "passive"))
      (node (ref "C6") (pin "1") (pinfunction "1_1") (pintype "passive"))
      (node (ref "R3") (pin "2") (pinfunction "2_2") (pintype "passive"))
      (node (ref "U2") (pin "13") (pinfunction "AVDDL_13") (pintype "passive"))
      (node (ref "U2") (pin "19") (pinfunction "AVDDL_19") (pintype "passive"))
      (node (ref "U2") (pin "44") (pinfunction "AVDDL_44") (pintype "passive"))
      (node (ref "U2") (pin "8") (pinfunction "AVDDL_8") (pintype "passive"))
    )
    (net (code "74") (name "Net-(CON1-Pad12)") (class "Default")
      (node (ref "CON1") (pin "12") (pinfunction "12_12") (pintype "passive"))
      (node (ref "R12") (pin "1") (pinfunction "1_1") (pintype "passive"))
    )
    (net (code "75") (name "Net-(CON1-Pad13)") (class "Default")
      (node (ref "CON1") (pin "13") (pinfunction "13_13") (pintype "passive"))
      (node (ref "R13") (pin "1") (pinfunction "1_1") (pintype "passive"))
    )
    (net (code "76") (name "Net-(CON1-Pad14)") (class "Default")
      (node (ref "CON1") (pin "14") (pinfunction "14_14") (pintype "passive"))
      (node (ref "R15") (pin "1") (pinfunction "1_1") (pintype "passive"))
    )
    (net (code "77") (name "Net-(CON2-VCC)") (class "Default")
      (node (ref "C29") (pin "2") (pinfunction "2_2") (pintype "passive"))
      (node (ref "C30") (pin "2") (pinfunction "2_2") (pintype "passive"))
      (node (ref "C31") (pin "2") (pinfunction "2_2") (pintype "passive"))
      (node (ref "C32") (pin "2") (pinfunction "2_2") (pintype "passive"))
      (node (ref "CON2") (pin "4") (pinfunction "VCC_4") (pintype "passive"))
      (node (ref "CON3") (pin "4") (pinfunction "VCC_4") (pintype "passive"))
      (node (ref "R20") (pin "1") (pinfunction "1_1") (pintype "passive"))
      (node (ref "R21") (pin "2") (pinfunction "2_2") (pintype "passive"))
      (node (ref "R22") (pin "2") (pinfunction "2_2") (pintype "passive"))
      (node (ref "R23") (pin "2") (pinfunction "2_2") (pintype "passive"))
      (node (ref "R24") (pin "2") (pinfunction "2_2") (pintype "passive"))
      (node (ref "R25") (pin "2") (pinfunction "2_2") (pintype "passive"))
      (node (ref "R26") (pin "2") (pinfunction "2_2") (pintype "passive"))
    )
    (net (code "78") (name "Net-(CON4-5V)") (class "Default")
      (node (ref "C23") (pin "1") (pinfunction "1_1") (pintype "passive"))
      (node (ref "CON4") (pin "1") (pinfunction "5V_1") (pintype "passive"))
      (node (ref "R27") (pin "1") (pinfunction "1_1") (pintype "passive"))
    )
    (net (code "79") (name "Net-(CON4-D+)") (class "Default")
      (node (ref "CON4") (pin "3") (pinfunction "D+_3") (pintype "passive"))
      (node (ref "R33") (pin "1") (pinfunction "1_1") (pintype "passive"))
    )
    (net (code "80") (name "Net-(CON4-D-)") (class "Default")
      (node (ref "CON4") (pin "2") (pinfunction "D-_2") (pintype "passive"))
      (node (ref "R32") (pin "1") (pinfunction "1_1") (pintype "passive"))
    )
    (net (code "81") (name "Net-(CON4-ID)") (class "Default")
      (node (ref "CON4") (pin "4") (pinfunction "ID_4") (pintype "passive"))
      (node (ref "R35") (pin "1") (pinfunction "1_1") (pintype "passive"))
    )
    (net (code "82") (name "Net-(CON5-3-Pad8)") (class "Default")
      (node (ref "CON5") (pin "8") (pinfunction "3_8") (pintype "passive"))
      (node (ref "CON5") (pin "9") (pinfunction "3_9") (pintype "passive"))
    )
    (net (code "83") (name "Net-(CON5-3-Pad10)") (class "Default")
      (node (ref "CON5") (pin "10") (pinfunction "3_10") (pintype "passive"))
      (node (ref "R39") (pin "1") (pinfunction "1_1") (pintype "passive"))
      (node (ref "R40") (pin "1") (pinfunction "1_1") (pintype "passive"))
    )
    (net (code "84") (name "Net-(CON5-RSVD)") (class "Default")
      (node (ref "CON5") (pin "18") (pinfunction "RSVD_18") (pintype "passive"))
      (node (ref "R45") (pin "1") (pinfunction "1_1") (pintype "passive"))
    )
    (net (code "85") (name "Net-(D2-A-Pad1)") (class "Default")
      (node (ref "D2") (pin "1") (pinfunction "A_1") (pintype "passive"))
      (node (ref "R44") (pin "1") (pinfunction "1_1") (pintype "passive"))
    )
    (net (code "86") (name "Net-(D2-C)") (class "Default")
      (node (ref "D2") (pin "3") (pinfunction "C_3") (pintype "passive"))
      (node (ref "Q6") (pin "1") (pinfunction "C_1") (pintype "passive"))
    )
    (net (code "87") (name "Net-(D3-A)") (class "Default")
      (node (ref "D3") (pin "1") (pinfunction "A_1") (pintype "passive"))
      (node (ref "R47") (pin "2") (pinfunction "2_2") (pintype "passive"))
    )
    (net (code "88") (name "Net-(Q1-B)") (class "Default")
      (node (ref "Q1") (pin "2") (pinfunction "B_2") (pintype "passive"))
      (node (ref "R18") (pin "1") (pinfunction "1_1") (pintype "passive"))
      (node (ref "R19") (pin "1") (pinfunction "1_1") (pintype "passive"))
    )
    (net (code "89") (name "Net-(Q1-C)") (class "Default")
      (node (ref "Q1") (pin "3") (pinfunction "C_3") (pintype "passive"))
      (node (ref "R16") (pin "2") (pinfunction "2_2") (pintype "passive"))
      (node (ref "U3") (pin "11") (pinfunction "T1IN_11") (pintype "passive"))
    )
    (net (code "90") (name "Net-(Q2-B)") (class "Default")
      (node (ref "Q2") (pin "2") (pinfunction "B_2") (pintype "passive"))
      (node (ref "R29") (pin "1") (pinfunction "1_1") (pintype "passive"))
      (node (ref "R30") (pin "2") (pinfunction "2_2") (pintype "passive"))
    )
    (net (code "91") (name "Net-(Q3-B)") (class "Default")
      (node (ref "Q3") (pin "2") (pinfunction "B_2") (pintype "passive"))
      (node (ref "R28") (pin "1") (pinfunction "1_1") (pintype "passive"))
      (node (ref "R34") (pin "2") (pinfunction "2_2") (pintype "passive"))
    )
    (net (code "92") (name "Net-(Q3-C)") (class "Default")
      (node (ref "Q3") (pin "3") (pinfunction "C_3") (pintype "passive"))
      (node (ref "R30") (pin "1") (pinfunction "1_1") (pintype "passive"))
    )
    (net (code "93") (name "Net-(Q4-D)") (class "Default")
      (node (ref "C40") (pin "1") (pinfunction "1_1") (pintype "passive"))
      (node (ref "CON5") (pin "14") (pinfunction "5V_14") (pintype "passive"))
      (node (ref "CON5") (pin "15") (pinfunction "5V_15") (pintype "passive"))
      (node (ref "CON5") (pin "16") (pinfunction "5V_16") (pintype "passive"))
      (node (ref "Q4") (pin "1") (pinfunction "D_1") (pintype "passive"))
      (node (ref "R47") (pin "1") (pinfunction "1_1") (pintype "passive"))
    )
    (net (code "94") (name "Net-(Q4-G)") (class "Default")
      (node (ref "CON5") (pin "20") (pinfunction "12V_20") (pintype "passive"))
      (node (ref "CON5") (pin "21") (pinfunction "12V_21") (pintype "passive"))
      (node (ref "CON5") (pin "22") (pinfunction "12V_22") (pintype "passive"))
      (node (ref "D2") (pin "2") (pinfunction "A_2") (pintype "passive"))
      (node (ref "Q4") (pin "2") (pinfunction "G_2") (pintype "passive"))
      (node (ref "Q5") (pin "1") (pinfunction "D_1") (pintype "passive"))
      (node (ref "R41") (pin "2") (pinfunction "2_2") (pintype "passive"))
    )
    (net (code "95") (name "Net-(Q5-G)") (class "Default")
      (node (ref "Q5") (pin "2") (pinfunction "G_2") (pintype "passive"))
      (node (ref "R42") (pin "2") (pinfunction "2_2") (pintype "passive"))
      (node (ref "R44") (pin "2") (pinfunction "2_2") (pintype "passive"))
    )
    (net (code "96") (name "Net-(Q6-B)") (class "Default")
      (node (ref "Q6") (pin "2") (pinfunction "B_2") (pintype "passive"))
      (node (ref "R43") (pin "2") (pinfunction "2_2") (pintype "passive"))
      (node (ref "R46") (pin "1") (pinfunction "1_1") (pintype "passive"))
    )
    (net (code "97") (name "Net-(U2-AVDD33)") (class "Default")
      (node (ref "C13") (pin "2") (pinfunction "2_2") (pintype "passive"))
      (node (ref "C14") (pin "2") (pinfunction "2_2") (pintype "passive"))
      (node (ref "R11") (pin "2") (pinfunction "2_2") (pintype "passive"))
      (node (ref "U2") (pin "16") (pinfunction "AVDD33_16") (pintype "passive"))
    )
    (net (code "98") (name "Net-(U2-CLK125M)") (class "Default")
      (node (ref "R17") (pin "2") (pinfunction "2_2") (pintype "passive"))
      (node (ref "U2") (pin "25") (pinfunction "CLK125M_25") (pintype "passive"))
    )
    (net (code "99") (name "Net-(U2-GTX_CLK)") (class "Default")
      (node (ref "RP2") (pin "1") (pinfunction "1_1") (pintype "passive"))
      (node (ref "U2") (pin "35") (pinfunction "GTX_CLK_35") (pintype "passive"))
    )
    (net (code "100") (name "Net-(U2-LX)") (class "Default")
      (node (ref "L1") (pin "1") (pinfunction "1_1") (pintype "passive"))
      (node (ref "U2") (pin "3") (pinfunction "LX_3") (pintype "passive"))
    )
    (net (code "101") (name "Net-(U2-RBIAS)") (class "Default")
      (node (ref "R10") (pin "2") (pinfunction "2_2") (pintype "passive"))
      (node (ref "U2") (pin "9") (pinfunction "RBIAS_9") (pintype "passive"))
    )
    (net (code "102") (name "Net-(U2-RXD0)") (class "Default")
      (node (ref "RP3") (pin "1") (pinfunction "1_1") (pintype "passive"))
      (node (ref "RP4") (pin "8") (pinfunction "8_8") (pintype "passive"))
      (node (ref "U2") (pin "31") (pinfunction "RXD0_31") (pintype "passive"))
    )
    (net (code "103") (name "Net-(U2-RXD1)") (class "Default")
      (node (ref "RP3") (pin "2") (pinfunction "2_2") (pintype "passive"))
      (node (ref "RP4") (pin "7") (pinfunction "7_7") (pintype "passive"))
      (node (ref "U2") (pin "30") (pinfunction "RXD1_30") (pintype "passive"))
    )
    (net (code "104") (name "Net-(U2-RXD2)") (class "Default")
      (node (ref "RP3") (pin "3") (pinfunction "3_3") (pintype "passive"))
      (node (ref "RP4") (pin "6") (pinfunction "6_6") (pintype "passive"))
      (node (ref "U2") (pin "28") (pinfunction "RXD2_28") (pintype "passive"))
    )
    (net (code "105") (name "Net-(U2-RXD3)") (class "Default")
      (node (ref "RP3") (pin "4") (pinfunction "4_4") (pintype "passive"))
      (node (ref "RP4") (pin "5") (pinfunction "5_5") (pintype "passive"))
      (node (ref "U2") (pin "27") (pinfunction "RXD3_27") (pintype "passive"))
    )
    (net (code "106") (name "Net-(U2-RX_CLK)") (class "Default")
      (node (ref "RP2") (pin "3") (pinfunction "3_3") (pintype "passive"))
      (node (ref "RP5") (pin "6") (pinfunction "6_6") (pintype "passive"))
      (node (ref "U2") (pin "33") (pinfunction "RX_CLK_33") (pintype "passive"))
    )
    (net (code "107") (name "Net-(U2-RX_DV)") (class "Default")
      (node (ref "RP2") (pin "4") (pinfunction "4_4") (pintype "passive"))
      (node (ref "RP5") (pin "5") (pinfunction "5_5") (pintype "passive"))
      (node (ref "U2") (pin "32") (pinfunction "RX_DV_32") (pintype "passive"))
    )
    (net (code "108") (name "Net-(U2-SD)") (class "Default")
      (node (ref "R9") (pin "2") (pinfunction "2_2") (pintype "passive"))
      (node (ref "U2") (pin "41") (pinfunction "SD_41") (pintype "passive"))
    )
    (net (code "109") (name "Net-(U2-TXD0)") (class "Default")
      (node (ref "RP1") (pin "4") (pinfunction "4_4") (pintype "passive"))
      (node (ref "U2") (pin "36") (pinfunction "TXD0_36") (pintype "passive"))
    )
    (net (code "110") (name "Net-(U2-TXD1)") (class "Default")
      (node (ref "RP1") (pin "3") (pinfunction "3_3") (pintype "passive"))
      (node (ref "U2") (pin "37") (pinfunction "TXD1_37") (pintype "passive"))
    )
    (net (code "111") (name "Net-(U2-TXD2)") (class "Default")
      (node (ref "RP1") (pin "2") (pinfunction "2_2") (pintype "passive"))
      (node (ref "U2") (pin "38") (pinfunction "TXD2_38") (pintype "passive"))
    )
    (net (code "112") (name "Net-(U2-TXD3)") (class "Default")
      (node (ref "RP1") (pin "1") (pinfunction "1_1") (pintype "passive"))
      (node (ref "U2") (pin "39") (pinfunction "TXD3_39") (pintype "passive"))
    )
    (net (code "113") (name "Net-(U2-TX_EN)") (class "Default")
      (node (ref "RP2") (pin "2") (pinfunction "2_2") (pintype "passive"))
      (node (ref "U2") (pin "34") (pinfunction "TX_EN_34") (pintype "passive"))
    )
    (net (code "114") (name "Net-(U2-VDD33)") (class "Default")
      (node (ref "C7") (pin "1") (pinfunction "1_1") (pintype "passive"))
      (node (ref "C9") (pin "1") (pinfunction "1_1") (pintype "passive"))
      (node (ref "R11") (pin "1") (pinfunction "1_1") (pintype "passive"))
      (node (ref "R4") (pin "1") (pinfunction "1_1") (pintype "passive"))
      (node (ref "R5") (pin "1") (pinfunction "1_1") (pintype "passive"))
      (node (ref "R7") (pin "2") (pinfunction "2_2") (pintype "passive"))
      (node (ref "R8") (pin "2") (pinfunction "2_2") (pintype "passive"))
      (node (ref "U2") (pin "4") (pinfunction "VDD33_4") (pintype "passive"))
    )
    (net (code "115") (name "Net-(U2-VDDIO_REG)") (class "Default")
      (node (ref "C20") (pin "1") (pinfunction "1_1") (pintype "passive"))
      (node (ref "C21") (pin "1") (pinfunction "1_1") (pintype "passive"))
      (node (ref "RP4") (pin "1") (pinfunction "1_1") (pintype "passive"))
      (node (ref "U2") (pin "29") (pinfunction "VDDIO_REG_29") (pintype "passive"))
    )
    (net (code "116") (name "Net-(U2-{slash}RST)") (class "Default")
      (node (ref "R6") (pin "2") (pinfunction "2_2") (pintype "passive"))
      (node (ref "U2") (pin "2") (pinfunction "/RST_2") (pintype "passive"))
    )
    (net (code "117") (name "Net-(U3-C1+)") (class "Default")
      (node (ref "C12") (pin "2") (pinfunction "2_2") (pintype "passive"))
      (node (ref "U3") (pin "1") (pinfunction "C1+_1") (pintype "passive"))
    )
    (net (code "118") (name "Net-(U3-C1-)") (class "Default")
      (node (ref "C12") (pin "1") (pinfunction "1_1") (pintype "passive"))
      (node (ref "U3") (pin "3") (pinfunction "C1-_3") (pintype "passive"))
    )
    (net (code "119") (name "Net-(U3-C2+)") (class "Default")
      (node (ref "C17") (pin "2") (pinfunction "2_2") (pintype "passive"))
      (node (ref "U3") (pin "4") (pinfunction "C2+_4") (pintype "passive"))
    )
    (net (code "120") (name "Net-(U3-C2-)") (class "Default")
      (node (ref "C17") (pin "1") (pinfunction "1_1") (pintype "passive"))
      (node (ref "U3") (pin "5") (pinfunction "C2-_5") (pintype "passive"))
    )
    (net (code "121") (name "Net-(U3-R1IN)") (class "Default")
      (node (ref "J2") (pin "2") (pinfunction "2_2") (pintype "passive"))
      (node (ref "U3") (pin "13") (pinfunction "R1IN_13") (pintype "passive"))
    )
    (net (code "122") (name "Net-(U3-R1OUT)") (class "Default")
      (node (ref "R14") (pin "1") (pinfunction "1_1") (pintype "passive"))
      (node (ref "U3") (pin "12") (pinfunction "R1OUT_12") (pintype "passive"))
    )
    (net (code "123") (name "Net-(U3-T1OUT)") (class "Default")
      (node (ref "J2") (pin "3") (pinfunction "3_3") (pintype "passive"))
      (node (ref "U3") (pin "14") (pinfunction "T1OUT_14") (pintype "passive"))
    )
    (net (code "124") (name "Net-(U3-V+)") (class "Default")
      (node (ref "C10") (pin "2") (pinfunction "2_2") (pintype "passive"))
      (node (ref "U3") (pin "2") (pinfunction "V+_2") (pintype "passive"))
    )
    (net (code "125") (name "Net-(U3-V-)") (class "Default")
      (node (ref "C18") (pin "2") (pinfunction "2_2") (pintype "passive"))
      (node (ref "U3") (pin "6") (pinfunction "V-_6") (pintype "passive"))
    )
    (net (code "126") (name "OTG_VBUS") (class "Default")
      (node (ref "C24") (pin "1") (pinfunction "1_1") (pintype "passive"))
      (node (ref "C25") (pin "1") (pinfunction "1_1") (pintype "passive"))
      (node (ref "Q2") (pin "3") (pinfunction "E_3") (pintype "passive"))
      (node (ref "R27") (pin "2") (pinfunction "2_2") (pintype "passive"))
      (node (ref "R29") (pin "2") (pinfunction "2_2") (pintype "passive"))
    )
    (net (code "127") (name "USB_OTG_VBUS") (class "Default")
      (node (ref "Q2") (pin "1") (pinfunction "C_1") (pintype "passive"))
      (node (ref "R31") (pin "2") (pinfunction "2_2") (pintype "passive"))
    )
    (net (code "128") (name "VDD_5V") (class "Default")
      (node (ref "Q4") (pin "3") (pinfunction "S_3") (pintype "passive"))
      (node (ref "R41") (pin "1") (pinfunction "1_1") (pintype "passive"))
    )
    (net (code "129") (name "VDD_12V") (class "Default")
      (node (ref "Q5") (pin "3") (pinfunction "S_3") (pintype "passive"))
      (node (ref "R42") (pin "1") (pinfunction "1_1") (pintype "passive"))
    )
    (net (code "130") (name "unconnected-(CON1-Pad2)") (class "Default")
      (node (ref "CON1") (pin "2") (pinfunction "2_2") (pintype "passive"))
    )
    (net (code "131") (name "unconnected-(J2-Pad1)") (class "Default")
      (node (ref "J2") (pin "1") (pinfunction "1_1") (pintype "passive"))
    )
    (net (code "132") (name "unconnected-(J2-Pad4)") (class "Default")
      (node (ref "J2") (pin "4") (pinfunction "4_4") (pintype "passive"))
    )
    (net (code "133") (name "unconnected-(J2-Pad6)") (class "Default")
      (node (ref "J2") (pin "6") (pinfunction "6_6") (pintype "passive"))
    )
    (net (code "134") (name "unconnected-(J2-Pad7)") (class "Default")
      (node (ref "J2") (pin "7") (pinfunction "7_7") (pintype "passive"))
    )
    (net (code "135") (name "unconnected-(J2-Pad8)") (class "Default")
      (node (ref "J2") (pin "8") (pinfunction "8_8") (pintype "passive"))
    )
    (net (code "136") (name "unconnected-(J2-Pad9)") (class "Default")
      (node (ref "J2") (pin "9") (pinfunction "9_9") (pintype "passive"))
    )
    (net (code "137") (name "unconnected-(U2-PPS-Pad22)") (class "Default")
      (node (ref "U2") (pin "22") (pinfunction "PPS_22") (pintype "passive"))
    )
    (net (code "138") (name "unconnected-(U2-SIN-Pad45)") (class "Default")
      (node (ref "U2") (pin "45") (pinfunction "SIN_45") (pintype "passive"))
    )
    (net (code "139") (name "unconnected-(U2-SIP-Pad46)") (class "Default")
      (node (ref "U2") (pin "46") (pinfunction "SIP_46") (pintype "passive"))
    )
    (net (code "140") (name "unconnected-(U2-SON-Pad42)") (class "Default")
      (node (ref "U2") (pin "42") (pinfunction "SON_42") (pintype "passive"))
    )
    (net (code "141") (name "unconnected-(U2-SOP-Pad43)") (class "Default")
      (node (ref "U2") (pin "43") (pinfunction "SOP_43") (pintype "passive"))
    )
    (net (code "142") (name "unconnected-(U3-R2IN-Pad8)") (class "Default")
      (node (ref "U3") (pin "8") (pinfunction "R2IN_8") (pintype "passive"))
    )
    (net (code "143") (name "unconnected-(U3-R2OUT-Pad9)") (class "Default")
      (node (ref "U3") (pin "9") (pinfunction "R2OUT_9") (pintype "passive"))
    )
    (net (code "144") (name "unconnected-(U3-T2IN-Pad10)") (class "Default")
      (node (ref "U3") (pin "10") (pinfunction "T2IN_10") (pintype "passive"))
    )
    (net (code "145") (name "unconnected-(U3-T2OUT-Pad7)") (class "Default")
      (node (ref "U3") (pin "7") (pinfunction "T2OUT_7") (pintype "passive"))
    )
  )
)
